# core.net
KiCad netlist of a schematic drawn in EAGLE
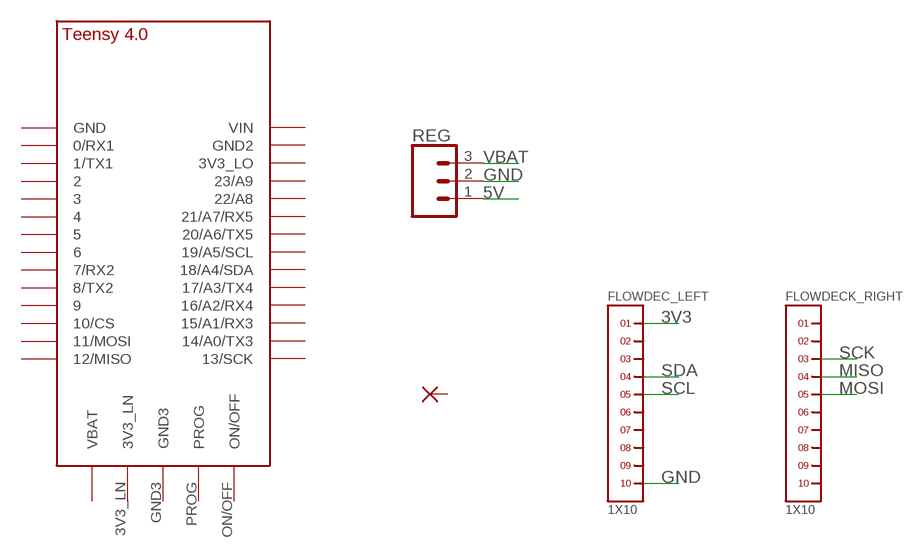
[diagram p0: schematic, sheet 1]

(export (version "E")
  (design (tool "Eeschema 10.0.6"))
  (components
    (comp (ref "FLOWDECK_RIGHT")
      (value "1X10")
      (footprint "eagle-import:1X10")
      (libsource (lib "eagle-import") (part "1X10"))
    )
    (comp (ref "FLOWDEC_LEFT")
      (value "1X10")
      (footprint "eagle-import:1X10")
      (libsource (lib "eagle-import") (part "1X10"))
    )
    (comp (ref "PAD18")
      (value "SMD2")
      (footprint "eagle-import:SMD1,27-2,54")
      (libsource (lib "eagle-import") (part "SMD2"))
    )
    (comp (ref "REG")
      (value "CONN_031X03_NO_SILK")
      (footprint "eagle-import:1X03_NO_SILK")
      (libsource (lib "eagle-import") (part "CONN_031X03_NO_SILK"))
    )
    (comp (ref "U$1")
      (value "TEENSY_4.0")
      (footprint "eagle-import:TEENSY_4.0")
      (libsource (lib "eagle-import") (part "TEENSY_4.0"))
    )
  )
  (nets
    (net (code "1") (name "/3V3") (class "Default")
      (node (ref "FLOWDEC_LEFT") (pin "1") (pinfunction "1_1") (pintype "bidirectional"))
    )
    (net (code "2") (name "/5V") (class "Default")
      (node (ref "REG") (pin "1") (pinfunction "1_1") (pintype "passive"))
    )
    (net (code "3") (name "/GND") (class "Default")
      (node (ref "FLOWDEC_LEFT") (pin "10") (pinfunction "10_10") (pintype "bidirectional"))
      (node (ref "REG") (pin "2") (pinfunction "2_2") (pintype "passive"))
    )
    (net (code "4") (name "/MISO") (class "Default")
      (node (ref "FLOWDECK_RIGHT") (pin "4") (pinfunction "4_4") (pintype "bidirectional"))
    )
    (net (code "5") (name "/MOSI") (class "Default")
      (node (ref "FLOWDECK_RIGHT") (pin "5") (pinfunction "5_5") (pintype "bidirectional"))
    )
    (net (code "6") (name "/SCK") (class "Default")
      (node (ref "FLOWDECK_RIGHT") (pin "3") (pinfunction "3_3") (pintype "bidirectional"))
    )
    (net (code "7") (name "/SCL") (class "Default")
      (node (ref "FLOWDEC_LEFT") (pin "5") (pinfunction "5_5") (pintype "bidirectional"))
    )
    (net (code "8") (name "/SDA") (class "Default")
      (node (ref "FLOWDEC_LEFT") (pin "4") (pinfunction "4_4") (pintype "bidirectional"))
    )
    (net (code "9") (name "/VBAT") (class "Default")
      (node (ref "REG") (pin "3") (pinfunction "3_3") (pintype "passive"))
    )
    (net (code "10") (name "unconnected-(FLOWDECK_RIGHT-Pad1)") (class "Default")
      (node (ref "FLOWDECK_RIGHT") (pin "1") (pinfunction "1_1") (pintype "bidirectional"))
    )
    (net (code "11") (name "unconnected-(FLOWDECK_RIGHT-Pad2)") (class "Default")
      (node (ref "FLOWDECK_RIGHT") (pin "2") (pinfunction "2_2") (pintype "bidirectional"))
    )
    (net (code "12") (name "unconnected-(FLOWDECK_RIGHT-Pad6)") (class "Default")
      (node (ref "FLOWDECK_RIGHT") (pin "6") (pinfunction "6_6") (pintype "bidirectional"))
    )
    (net (code "13") (name "unconnected-(FLOWDECK_RIGHT-Pad7)") (class "Default")
      (node (ref "FLOWDECK_RIGHT") (pin "7") (pinfunction "7_7") (pintype "bidirectional"))
    )
    (net (code "14") (name "unconnected-(FLOWDECK_RIGHT-Pad8)") (class "Default")
      (node (ref "FLOWDECK_RIGHT") (pin "8") (pinfunction "8_8") (pintype "bidirectional"))
    )
    (net (code "15") (name "unconnected-(FLOWDECK_RIGHT-Pad9)") (class "Default")
      (node (ref "FLOWDECK_RIGHT") (pin "9") (pinfunction "9_9") (pintype "bidirectional"))
    )
    (net (code "16") (name "unconnected-(FLOWDECK_RIGHT-Pad10)") (class "Default")
      (node (ref "FLOWDECK_RIGHT") (pin "10") (pinfunction "10_10") (pintype "bidirectional"))
    )
    (net (code "17") (name "unconnected-(FLOWDEC_LEFT-Pad2)") (class "Default")
      (node (ref "FLOWDEC_LEFT") (pin "2") (pinfunction "2_2") (pintype "bidirectional"))
    )
    (net (code "18") (name "unconnected-(FLOWDEC_LEFT-Pad3)") (class "Default")
      (node (ref "FLOWDEC_LEFT") (pin "3") (pinfunction "3_3") (pintype "bidirectional"))
    )
    (net (code "19") (name "unconnected-(FLOWDEC_LEFT-Pad6)") (class "Default")
      (node (ref "FLOWDEC_LEFT") (pin "6") (pinfunction "6_6") (pintype "bidirectional"))
    )
    (net (code "20") (name "unconnected-(FLOWDEC_LEFT-Pad7)") (class "Default")
      (node (ref "FLOWDEC_LEFT") (pin "7") (pinfunction "7_7") (pintype "bidirectional"))
    )
    (net (code "21") (name "unconnected-(FLOWDEC_LEFT-Pad8)") (class "Default")
      (node (ref "FLOWDEC_LEFT") (pin "8") (pinfunction "8_8") (pintype "bidirectional"))
    )
    (net (code "22") (name "unconnected-(FLOWDEC_LEFT-Pad9)") (class "Default")
      (node (ref "FLOWDEC_LEFT") (pin "9") (pinfunction "9_9") (pintype "bidirectional"))
    )
    (net (code "23") (name "unconnected-(PAD18-P-Pad1)") (class "Default")
      (node (ref "PAD18") (pin "1") (pinfunction "P_1") (pintype "passive"))
    )
    (net (code "24") (name "unconnected-(U$1-0{slash}RX1-Pad0{slash}RX)") (class "Default")
      (node (ref "U$1") (pin "0/RX") (pinfunction "0/RX1_0/RX") (pintype "bidirectional"))
    )
    (net (code "25") (name "unconnected-(U$1-1{slash}TX1-Pad1{slash}TX)") (class "Default")
      (node (ref "U$1") (pin "1/TX") (pinfunction "1/TX1_1/TX") (pintype "bidirectional"))
    )
    (net (code "26") (name "unconnected-(U$1-3-Pad3{slash}CANTX)") (class "Default")
      (node (ref "U$1") (pin "3/CANTX") (pinfunction "3_3/CANTX") (pintype "bidirectional"))
    )
    (net (code "27") (name "unconnected-(U$1-4-Pad4{slash}CANRX)") (class "Default")
      (node (ref "U$1") (pin "4/CANRX") (pinfunction "4_4/CANRX") (pintype "bidirectional"))
    )
    (net (code "28") (name "unconnected-(U$1-7{slash}RX2-Pad7)") (class "Default")
      (node (ref "U$1") (pin "7") (pinfunction "7/RX2_7") (pintype "bidirectional"))
    )
    (net (code "29") (name "unconnected-(U$1-8{slash}TX2-Pad8)") (class "Default")
      (node (ref "U$1") (pin "8") (pinfunction "8/TX2_8") (pintype "bidirectional"))
    )
    (net (code "30") (name "unconnected-(U$1-9-Pad9{slash}CS)") (class "Default")
      (node (ref "U$1") (pin "9/CS") (pinfunction "9_9/CS") (pintype "bidirectional"))
    )
    (net (code "31") (name "unconnected-(U$1-14{slash}A0{slash}TX3-Pad14{slash}A0)") (class "Default")
      (node (ref "U$1") (pin "14/A0") (pinfunction "14/A0/TX3_14/A0") (pintype "bidirectional"))
    )
    (net (code "32") (name "unconnected-(U$1-15{slash}A1{slash}RX3-Pad15{slash}A1)") (class "Default")
      (node (ref "U$1") (pin "15/A1") (pinfunction "15/A1/RX3_15/A1") (pintype "bidirectional"))
    )
    (net (code "33") (name "unconnected-(U$1-16{slash}A2{slash}RX4-Pad16{slash}A2)") (class "Default")
      (node (ref "U$1") (pin "16/A2") (pinfunction "16/A2/RX4_16/A2") (pintype "bidirectional"))
    )
    (net (code "34") (name "unconnected-(U$1-17{slash}A3{slash}TX4-Pad17{slash}A3)") (class "Default")
      (node (ref "U$1") (pin "17/A3") (pinfunction "17/A3/TX4_17/A3") (pintype "bidirectional"))
    )
    (net (code "35") (name "unconnected-(U$1-20{slash}A6{slash}TX5-Pad20{slash}A6)") (class "Default")
      (node (ref "U$1") (pin "20/A6") (pinfunction "20/A6/TX5_20/A6") (pintype "bidirectional"))
    )
    (net (code "36") (name "unconnected-(U$1-21{slash}A7{slash}RX5-Pad21{slash}A7)") (class "Default")
      (node (ref "U$1") (pin "21/A7") (pinfunction "21/A7/RX5_21/A7") (pintype "bidirectional"))
    )
    (net (code "37") (name "unconnected-(U$1-Pad2)") (class "Default")
      (node (ref "U$1") (pin "2") (pinfunction "2_2") (pintype "bidirectional"))
    )
    (net (code "38") (name "unconnected-(U$1-Pad3V3_LN)") (class "Default")
      (node (ref "U$1") (pin "3V3_LN") (pinfunction "3V3_LN_3V3_LN") (pintype "bidirectional"))
    )
    (net (code "39") (name "unconnected-(U$1-Pad3V3_LO)") (class "Default")
      (node (ref "U$1") (pin "3V3_LO") (pinfunction "3V3_LO_3V3_LO") (pintype "bidirectional"))
    )
    (net (code "40") (name "unconnected-(U$1-Pad5)") (class "Default")
      (node (ref "U$1") (pin "5") (pinfunction "5_5") (pintype "bidirectional"))
    )
    (net (code "41") (name "unconnected-(U$1-Pad6)") (class "Default")
      (node (ref "U$1") (pin "6") (pinfunction "6_6") (pintype "bidirectional"))
    )
    (net (code "42") (name "unconnected-(U$1-Pad10{slash}CS)") (class "Default")
      (node (ref "U$1") (pin "10/CS") (pinfunction "10/CS_10/CS") (pintype "bidirectional"))
    )
    (net (code "43") (name "unconnected-(U$1-Pad11{slash}MOSI)") (class "Default")
      (node (ref "U$1") (pin "11/MOSI") (pinfunction "11/MOSI_11/MOSI") (pintype "bidirectional"))
    )
    (net (code "44") (name "unconnected-(U$1-Pad12{slash}MISO)") (class "Default")
      (node (ref "U$1") (pin "12/MISO") (pinfunction "12/MISO_12/MISO") (pintype "bidirectional"))
    )
    (net (code "45") (name "unconnected-(U$1-Pad13{slash}SCK)") (class "Default")
      (node (ref "U$1") (pin "13/SCK") (pinfunction "13/SCK_13/SCK") (pintype "bidirectional"))
    )
    (net (code "46") (name "unconnected-(U$1-Pad18{slash}A4{slash}SDA)") (class "Default")
      (node (ref "U$1") (pin "18/A4/SDA") (pinfunction "18/A4/SDA_18/A4/SDA") (pintype "bidirectional"))
    )
    (net (code "47") (name "unconnected-(U$1-Pad19{slash}A5{slash}SCL)") (class "Default")
      (node (ref "U$1") (pin "19/A5/SCL") (pinfunction "19/A5/SCL_19/A5/SCL") (pintype "bidirectional"))
    )
    (net (code "48") (name "unconnected-(U$1-Pad22{slash}A8)") (class "Default")
      (node (ref "U$1") (pin "22/A8") (pinfunction "22/A8_22/A8") (pintype "bidirectional"))
    )
    (net (code "49") (name "unconnected-(U$1-Pad23{slash}A9)") (class "Default")
      (node (ref "U$1") (pin "23/A9") (pinfunction "23/A9_23/A9") (pintype "bidirectional"))
    )
    (net (code "50") (name "unconnected-(U$1-PadGND)") (class "Default")
      (node (ref "U$1") (pin "GND") (pinfunction "GND_GND") (pintype "bidirectional"))
    )
    (net (code "51") (name "unconnected-(U$1-PadGND2)") (class "Default")
      (node (ref "U$1") (pin "GND2") (pinfunction "GND2_GND2") (pintype "bidirectional"))
    )
    (net (code "52") (name "unconnected-(U$1-PadGND3)") (class "Default")
      (node (ref "U$1") (pin "GND3") (pinfunction "GND3_GND3") (pintype "bidirectional"))
    )
    (net (code "53") (name "unconnected-(U$1-PadON{slash}OFF)") (class "Default")
      (node (ref "U$1") (pin "ON/OFF") (pinfunction "ON/OFF_ON/OFF") (pintype "bidirectional"))
    )
    (net (code "54") (name "unconnected-(U$1-PadPROG)") (class "Default")
      (node (ref "U$1") (pin "PROG") (pinfunction "PROG_PROG") (pintype "bidirectional"))
    )
    (net (code "55") (name "unconnected-(U$1-PadVIN)") (class "Default")
      (node (ref "U$1") (pin "VIN") (pinfunction "VIN_VIN") (pintype "bidirectional"))
    )
    (net (code "56") (name "unconnected-(U$1-VBAT-PadVBAT\\)") (class "Default")
      (node (ref "U$1") (pin "VBAT\\") (pinfunction "VBAT_VBAT\\") (pintype "bidirectional"))
    )
  )
)
